# multipointMv2.net
KiCad netlist of a schematic drawn in EAGLE
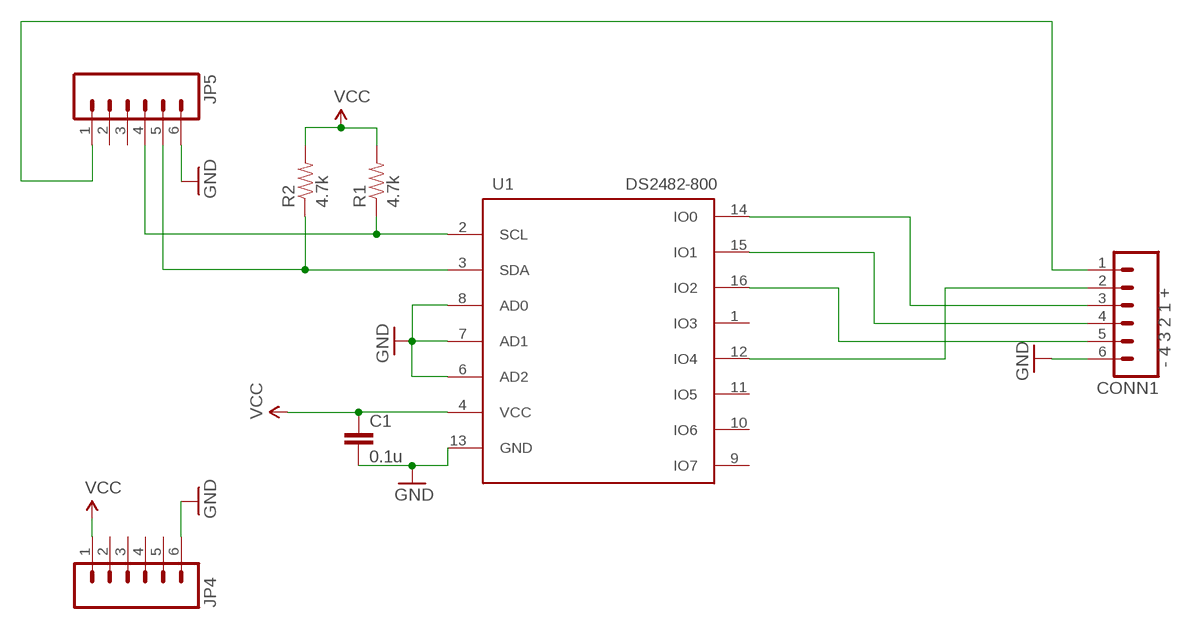
[diagram p0: schematic, sheet 1]

(export (version "E")
  (design (tool "Eeschema 10.0.6"))
  (components
    (comp (ref "C1")
      (value "0.1u")
      (footprint "eagle-import:0805")
      (libsource (lib "eagle-import") (part "CAP0805"))
    )
    (comp (ref "CONN1")
      (value "- 4 3 2 1 +")
      (footprint "eagle-import:1X06_LOCK_LONGPADS")
      (libsource (lib "eagle-import") (part "SparkFun-Connectors_M06LOCK_LONGPADS"))
    )
    (comp (ref "JP4")
      (value "M06LOCK_LONGPADS")
      (footprint "eagle-import:1X06_LOCK_LONGPADS")
      (libsource (lib "eagle-import") (part "M06LOCK_LONGPADS"))
    )
    (comp (ref "JP5")
      (value "M06LOCK_LONGPADS")
      (footprint "eagle-import:1X06_LOCK_LONGPADS")
      (libsource (lib "eagle-import") (part "M06LOCK_LONGPADS"))
    )
    (comp (ref "R1")
      (value "4.7k")
      (footprint "eagle-import:0805")
      (libsource (lib "eagle-import") (part "RESISTOR0805-RES"))
    )
    (comp (ref "R2")
      (value "4.7k")
      (footprint "eagle-import:0805")
      (libsource (lib "eagle-import") (part "RESISTOR0805-RES"))
    )
    (comp (ref "U1")
      (value "DS2482-800")
      (footprint "eagle-import:SO16")
      (libsource (lib "eagle-import") (part "DS2482-800"))
    )
  )
  (nets
    (net (code "1") (name "GND") (class "Default")
      (node (ref "C1") (pin "2") (pinfunction "2_2") (pintype "passive"))
      (node (ref "CONN1") (pin "6") (pinfunction "6_6") (pintype "passive"))
      (node (ref "JP4") (pin "6") (pinfunction "6_6") (pintype "passive"))
      (node (ref "JP5") (pin "6") (pinfunction "6_6") (pintype "passive"))
      (node (ref "U1") (pin "13") (pinfunction "GND_13") (pintype "bidirectional"))
      (node (ref "U1") (pin "6") (pinfunction "AD2_6") (pintype "bidirectional"))
      (node (ref "U1") (pin "7") (pinfunction "AD1_7") (pintype "bidirectional"))
      (node (ref "U1") (pin "8") (pinfunction "AD0_8") (pintype "bidirectional"))
    )
    (net (code "2") (name "Net-(CONN1-Pad1)") (class "Default")
      (node (ref "CONN1") (pin "1") (pinfunction "1_1") (pintype "passive"))
      (node (ref "JP5") (pin "1") (pinfunction "1_1") (pintype "passive"))
    )
    (net (code "3") (name "Net-(U1-IO0)") (class "Default")
      (node (ref "CONN1") (pin "3") (pinfunction "3_3") (pintype "passive"))
      (node (ref "U1") (pin "14") (pinfunction "IO0_14") (pintype "bidirectional"))
    )
    (net (code "4") (name "Net-(U1-IO1)") (class "Default")
      (node (ref "CONN1") (pin "4") (pinfunction "4_4") (pintype "passive"))
      (node (ref "U1") (pin "15") (pinfunction "IO1_15") (pintype "bidirectional"))
    )
    (net (code "5") (name "Net-(U1-IO2)") (class "Default")
      (node (ref "CONN1") (pin "5") (pinfunction "5_5") (pintype "passive"))
      (node (ref "U1") (pin "16") (pinfunction "IO2_16") (pintype "bidirectional"))
    )
    (net (code "6") (name "Net-(U1-IO4)") (class "Default")
      (node (ref "CONN1") (pin "2") (pinfunction "2_2") (pintype "passive"))
      (node (ref "U1") (pin "12") (pinfunction "IO4_12") (pintype "bidirectional"))
    )
    (net (code "7") (name "Net-(U1-SCL)") (class "Default")
      (node (ref "JP5") (pin "4") (pinfunction "4_4") (pintype "passive"))
      (node (ref "R1") (pin "1") (pinfunction "1_1") (pintype "passive"))
      (node (ref "U1") (pin "2") (pinfunction "SCL_2") (pintype "bidirectional"))
    )
    (net (code "8") (name "Net-(U1-SDA)") (class "Default")
      (node (ref "JP5") (pin "5") (pinfunction "5_5") (pintype "passive"))
      (node (ref "R2") (pin "1") (pinfunction "1_1") (pintype "passive"))
      (node (ref "U1") (pin "3") (pinfunction "SDA_3") (pintype "bidirectional"))
    )
    (net (code "9") (name "VCC") (class "Default")
      (node (ref "C1") (pin "1") (pinfunction "1_1") (pintype "passive"))
      (node (ref "JP4") (pin "1") (pinfunction "1_1") (pintype "passive"))
      (node (ref "R1") (pin "2") (pinfunction "2_2") (pintype "passive"))
      (node (ref "R2") (pin "2") (pinfunction "2_2") (pintype "passive"))
      (node (ref "U1") (pin "4") (pinfunction "VCC_4") (pintype "bidirectional"))
    )
    (net (code "10") (name "unconnected-(JP4-Pad2)") (class "Default")
      (node (ref "JP4") (pin "2") (pinfunction "2_2") (pintype "passive"))
    )
    (net (code "11") (name "unconnected-(JP4-Pad3)") (class "Default")
      (node (ref "JP4") (pin "3") (pinfunction "3_3") (pintype "passive"))
    )
    (net (code "12") (name "unconnected-(JP4-Pad4)") (class "Default")
      (node (ref "JP4") (pin "4") (pinfunction "4_4") (pintype "passive"))
    )
    (net (code "13") (name "unconnected-(JP4-Pad5)") (class "Default")
      (node (ref "JP4") (pin "5") (pinfunction "5_5") (pintype "passive"))
    )
    (net (code "14") (name "unconnected-(JP5-Pad2)") (class "Default")
      (node (ref "JP5") (pin "2") (pinfunction "2_2") (pintype "passive"))
    )
    (net (code "15") (name "unconnected-(JP5-Pad3)") (class "Default")
      (node (ref "JP5") (pin "3") (pinfunction "3_3") (pintype "passive"))
    )
    (net (code "16") (name "unconnected-(U1-IO3-Pad1)") (class "Default")
      (node (ref "U1") (pin "1") (pinfunction "IO3_1") (pintype "bidirectional"))
    )
    (net (code "17") (name "unconnected-(U1-IO5-Pad11)") (class "Default")
      (node (ref "U1") (pin "11") (pinfunction "IO5_11") (pintype "bidirectional"))
    )
    (net (code "18") (name "unconnected-(U1-IO6-Pad10)") (class "Default")
      (node (ref "U1") (pin "10") (pinfunction "IO6_10") (pintype "bidirectional"))
    )
    (net (code "19") (name "unconnected-(U1-IO7-Pad9)") (class "Default")
      (node (ref "U1") (pin "9") (pinfunction "IO7_9") (pintype "bidirectional"))
    )
  )
)
